# TPS54622_Schematic.net
KiCad netlist of a schematic drawn in Altium Designer
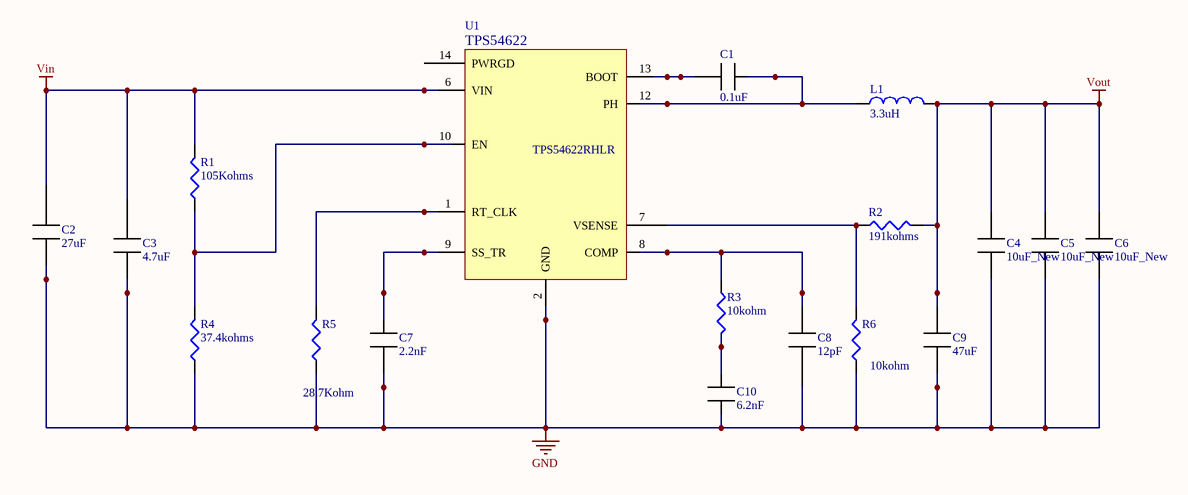
[diagram p0: TPS54622_Schematic.SchDoc]

(export (version "E")
  (design (tool "Eeschema 10.0.6"))
  (components
    (comp (ref "C1")
      (value "0.1uF")
      (footprint "C/R0805")
      (description "KEMET         C0805C104Z5VACTU.             CERAMIC CAPACITOR, 0.1UF, 50V, Y5V, +80,-20%, 0805")
      (fields
        (field (name "MANUFACTURER") "KEMET")
        (field (name "MANUFACTURER PART NUMBER") "C0805C104Z5VACTU")
      )
      (libsource (lib "TPS54622_Schematic_Library") (part "C0805C104Z5VACTU"))
    )
    (comp (ref "C2")
      (value "27uF")
      (footprint "CAPAE430X550N")
      (description "CAP ALUM POLY 27UF 20% 25V SMD")
      (fields
        (field (name "MANUFACTURER") "Panasonic")
        (field (name "MANUFACTURER PART NUMBER") "25SVPF27MX")
      )
      (libsource (lib "TPS54622_Schematic_Library") (part "25SVPF27MX"))
    )
    (comp (ref "C3")
      (value "4.7uF")
      (footprint "C/R0805")
      (description "CAP CER 4.7UF 10V Y5V 0805")
      (fields
        (field (name "MANUFACTURER") "Yageo")
        (field (name "MANUFACTURER PART NUMBER") "CC0805ZRY5V6BB475")
      )
      (libsource (lib "TPS54622_Schematic_Library") (part "CC0805ZRY5V6BB475"))
    )
    (comp (ref "C4")
      (value "10uF_New")
      (footprint "CAPPM7343X310N")
      (description "CAP TANT 10UF 35V 20% 2917")
      (fields
        (field (name "MANUFACTURER") "KEMET")
        (field (name "MANUFACTURER PART NUMBER") "T495D106M035ATE125")
      )
      (libsource (lib "TPS54622_Schematic_Library") (part "T495D106M035ATE125"))
    )
    (comp (ref "C5")
      (value "10uF_New")
      (footprint "CAPPM7343X310N")
      (description "CAP TANT 10UF 35V 20% 2917")
      (fields
        (field (name "MANUFACTURER") "KEMET")
        (field (name "MANUFACTURER PART NUMBER") "T495D106M035ATE125")
      )
      (libsource (lib "TPS54622_Schematic_Library") (part "T495D106M035ATE125"))
    )
    (comp (ref "C6")
      (value "10uF_New")
      (footprint "CAPPM7343X310N")
      (description "CAP TANT 10UF 35V 20% 2917")
      (fields
        (field (name "MANUFACTURER") "KEMET")
        (field (name "MANUFACTURER PART NUMBER") "T495D106M035ATE125")
      )
      (libsource (lib "TPS54622_Schematic_Library") (part "T495D106M035ATE125"))
    )
    (comp (ref "C7")
      (value "2.2nF")
      (footprint "C/R0805")
      (description "Cap Ceramic 0.0022uF 50V X7R 10% Pad SMD 0805 125C Bulk")
      (fields
        (field (name "MANUFACTURER") "KEMET")
        (field (name "MANUFACTURER PART NUMBER") "C0805C222K5RAC")
      )
      (libsource (lib "TPS54622_Schematic_Library") (part "C0805C222K5RAC"))
    )
    (comp (ref "C8")
      (value "12pF")
      (footprint "C/R0805")
      (description "CAP CER 12PF 50V C0G/NPO 0805")
      (fields
        (field (name "MANUFACTURER") "Yageo")
        (field (name "MANUFACTURER PART NUMBER") "CC0805JRNPO9BN120")
      )
      (libsource (lib "TPS54622_Schematic_Library") (part "CC0805JRNPO9BN120"))
    )
    (comp (ref "C9")
      (value "47uF")
      (footprint "C/R0805")
      (description "47µF 6.3V Ceramic Capacitor X5R 0805 (2012 Metric) 0.079\" L x 0.049\" W (2.00mm x 1.25mm)")
      (fields
        (field (name "MANUFACTURER") "Murata")
        (field (name "MANUFACTURER PART NUMBER") "GRM21BR60J476ME15K")
      )
      (libsource (lib "TPS54622_Schematic_Library") (part "GRM21BR60J476ME15K"))
    )
    (comp (ref "C10")
      (value "6.2nF")
      (footprint "C/R0805")
      (description "CAP CER 6200PF 50V C0G/NP0 0805")
      (fields
        (field (name "MANUFACTURER") "Murata")
        (field (name "MANUFACTURER PART NUMBER") "GRM2195C1H622JA01D")
      )
      (libsource (lib "TPS54622_Schematic_Library") (part "GRM2195C1H622JA01D"))
    )
    (comp (ref "L1")
      (value "3.3uH")
      (footprint "C/R0805")
      (fields
        (field (name "MANUFACTURER") "Taiyo Yuden")
        (field (name "MANUFACTURER PART NUMBER") "BRC2012T3R3MD")
        (field (name "TOLERANCE") "±20%")
      )
      (libsource (lib "TPS54622_Schematic_Library") (part "BRC2012T3R3MD"))
    )
    (comp (ref "R1")
      (value "105Kohms")
      (footprint "C/R0805")
      (description "RESISTOR, 0805, 105K, 0.1%, 0.125W")
      (fields
        (field (name "MANUFACTURER") "Panasonic")
        (field (name "MANUFACTURER PART NUMBER") "ERA-6AEB1053V")
      )
      (libsource (lib "TPS54622_Schematic_Library") (part "ERA-6AEB1053V"))
    )
    (comp (ref "R2")
      (value "191kohms")
      (footprint "C/R0805")
      (description "Res Thin Film 0805 191K Ohm 0.1% 1/8W 25ppm/C Molded SMD Punched Carrier T/R")
      (fields
        (field (name "MANUFACTURER") "Panasonic")
        (field (name "MANUFACTURER PART NUMBER") "ERA-6AEB1913V")
      )
      (libsource (lib "TPS54622_Schematic_Library") (part "ERA-6AEB1913V"))
    )
    (comp (ref "R3")
      (value "10kohm")
      (footprint "C/R0805")
      (description "RES SMD 10K OHM 1/4W 0805 WIDE")
      (fields (field (name "MANUFACTURER") "Rohm") (field (name "MANUFACTURER PART NUMBER") "LTR10EZPJ103"))
      (libsource (lib "TPS54622_Schematic_Library") (part "LTR10EZPJ103"))
    )
    (comp (ref "R4")
      (value "37.4kohms")
      (footprint "C/R0805")
      (description "Metal film resistor 37.4 kΩ SMD 0805 0.125 W")
      (fields
        (field (name "MANUFACTURER") "Panasonic")
        (field (name "MANUFACTURER PART NUMBER") "ERA6AEB3742V")
      )
      (libsource (lib "TPS54622_Schematic_Library") (part "ERA6AEB3742V"))
    )
    (comp (ref "R5")
      (value "28.7Kohm")
      (footprint "C/R0805")
      (description "RES SMD 28.7K OHM 0.1% 1/8W 0805")
      (fields
        (field (name "MANUFACTURER") "Susumu")
        (field (name "MANUFACTURER PART NUMBER") "RG2012P-2872-B-T5")
      )
      (libsource (lib "TPS54622_Schematic_Library") (part "RG2012P-2872-B-T5"))
    )
    (comp (ref "R6")
      (value "10kohm")
      (footprint "C/R0805")
      (description "RES SMD 10K OHM 1/4W 0805 WIDE")
      (fields (field (name "MANUFACTURER") "Rohm") (field (name "MANUFACTURER PART NUMBER") "LTR10EZPJ103"))
      (libsource (lib "TPS54622_Schematic_Library") (part "LTR10EZPJ103"))
    )
    (comp (ref "U1")
      (value "TPS54622RHLR")
      (footprint "QFN50P350X350X100-15N")
      (description "IC REG BUCK ADJ 6A SYNC 14QFN")
      (fields (field (name "MANUFACTURER") "Texas Instruments"))
      (libsource (lib "TPS54622_Schematic_Library") (part "TPS54622RHLR"))
    )
  )
  (nets
    (net (code "1") (name "GND") (class "Default")
      (node (ref "C10") (pin "1") (pinfunction "1_1") (pintype "passive"))
      (node (ref "C2") (pin "1") (pinfunction "1_1") (pintype "passive"))
      (node (ref "C3") (pin "1") (pinfunction "1_1") (pintype "passive"))
      (node (ref "C7") (pin "1") (pinfunction "1_1") (pintype "passive"))
      (node (ref "C8") (pin "2") (pinfunction "2_2") (pintype "passive"))
      (node (ref "C9") (pin "1") (pinfunction "1_1") (pintype "passive"))
      (node (ref "R4") (pin "1") (pinfunction "1_1") (pintype "passive"))
      (node (ref "R5") (pin "1") (pinfunction "1_1") (pintype "passive"))
      (node (ref "R6") (pin "1") (pinfunction "1_1") (pintype "passive"))
      (node (ref "U1") (pin "2") (pinfunction "GND_2") (pintype "passive"))
    )
    (net (code "2") (name "Net-(C10-Pad2)") (class "Default")
      (node (ref "C10") (pin "2") (pinfunction "2_2") (pintype "passive"))
      (node (ref "R3") (pin "2") (pinfunction "2_2") (pintype "passive"))
    )
    (net (code "3") (name "Net-(U1-BOOT)") (class "Default")
      (node (ref "C1") (pin "1") (pinfunction "1_1") (pintype "passive"))
      (node (ref "U1") (pin "13") (pinfunction "BOOT_13") (pintype "passive"))
    )
    (net (code "4") (name "Net-(U1-COMP)") (class "Default")
      (node (ref "C8") (pin "1") (pinfunction "1_1") (pintype "passive"))
      (node (ref "R3") (pin "1") (pinfunction "1_1") (pintype "passive"))
      (node (ref "U1") (pin "8") (pinfunction "COMP_8") (pintype "passive"))
    )
    (net (code "5") (name "Net-(U1-EN)") (class "Default")
      (node (ref "R1") (pin "1") (pinfunction "1_1") (pintype "passive"))
      (node (ref "R4") (pin "2") (pinfunction "2_2") (pintype "passive"))
      (node (ref "U1") (pin "10") (pinfunction "EN_10") (pintype "passive"))
    )
    (net (code "6") (name "Net-(U1-PH)") (class "Default")
      (node (ref "C1") (pin "2") (pinfunction "2_2") (pintype "passive"))
      (node (ref "L1") (pin "1") (pinfunction "1_1") (pintype "passive"))
      (node (ref "U1") (pin "12") (pinfunction "PH_12") (pintype "passive"))
    )
    (net (code "7") (name "Net-(U1-RT_CLK)") (class "Default")
      (node (ref "R5") (pin "2") (pinfunction "2_2") (pintype "passive"))
      (node (ref "U1") (pin "1") (pinfunction "RT_CLK_1") (pintype "passive"))
    )
    (net (code "8") (name "Net-(U1-SS_TR)") (class "Default")
      (node (ref "C7") (pin "2") (pinfunction "2_2") (pintype "passive"))
      (node (ref "U1") (pin "9") (pinfunction "SS_TR_9") (pintype "passive"))
    )
    (net (code "9") (name "Net-(U1-VSENSE)") (class "Default")
      (node (ref "R2") (pin "1") (pinfunction "1_1") (pintype "passive"))
      (node (ref "R6") (pin "2") (pinfunction "2_2") (pintype "passive"))
      (node (ref "U1") (pin "7") (pinfunction "VSENSE_7") (pintype "passive"))
    )
    (net (code "10") (name "Vin") (class "Default")
      (node (ref "C2") (pin "2") (pinfunction "2_2") (pintype "passive"))
      (node (ref "C3") (pin "2") (pinfunction "2_2") (pintype "passive"))
      (node (ref "R1") (pin "2") (pinfunction "2_2") (pintype "passive"))
      (node (ref "U1") (pin "6") (pinfunction "VIN_6") (pintype "passive"))
    )
    (net (code "11") (name "Vout") (class "Default")
      (node (ref "C9") (pin "2") (pinfunction "2_2") (pintype "passive"))
      (node (ref "L1") (pin "2") (pinfunction "2_2") (pintype "passive"))
      (node (ref "R2") (pin "2") (pinfunction "2_2") (pintype "passive"))
    )
    (net (code "12") (name "unconnected-(C4-Pad3)") (class "Default")
      (node (ref "C4") (pin "3") (pintype "passive"))
    )
    (net (code "13") (name "unconnected-(C4-Pad4)") (class "Default")
      (node (ref "C4") (pin "4") (pintype "passive"))
    )
    (net (code "14") (name "unconnected-(C5-Pad3)") (class "Default")
      (node (ref "C5") (pin "3") (pintype "passive"))
    )
    (net (code "15") (name "unconnected-(C5-Pad4)") (class "Default")
      (node (ref "C5") (pin "4") (pintype "passive"))
    )
    (net (code "16") (name "unconnected-(C6-Pad3)") (class "Default")
      (node (ref "C6") (pin "3") (pintype "passive"))
    )
    (net (code "17") (name "unconnected-(C6-Pad4)") (class "Default")
      (node (ref "C6") (pin "4") (pintype "passive"))
    )
    (net (code "18") (name "unconnected-(U1-PWRGD-Pad14)") (class "Default")
      (node (ref "U1") (pin "14") (pinfunction "PWRGD_14") (pintype "passive"))
    )
  )
)
